# CurrentSensor.net
KiCad netlist of a schematic drawn in Altium Designer
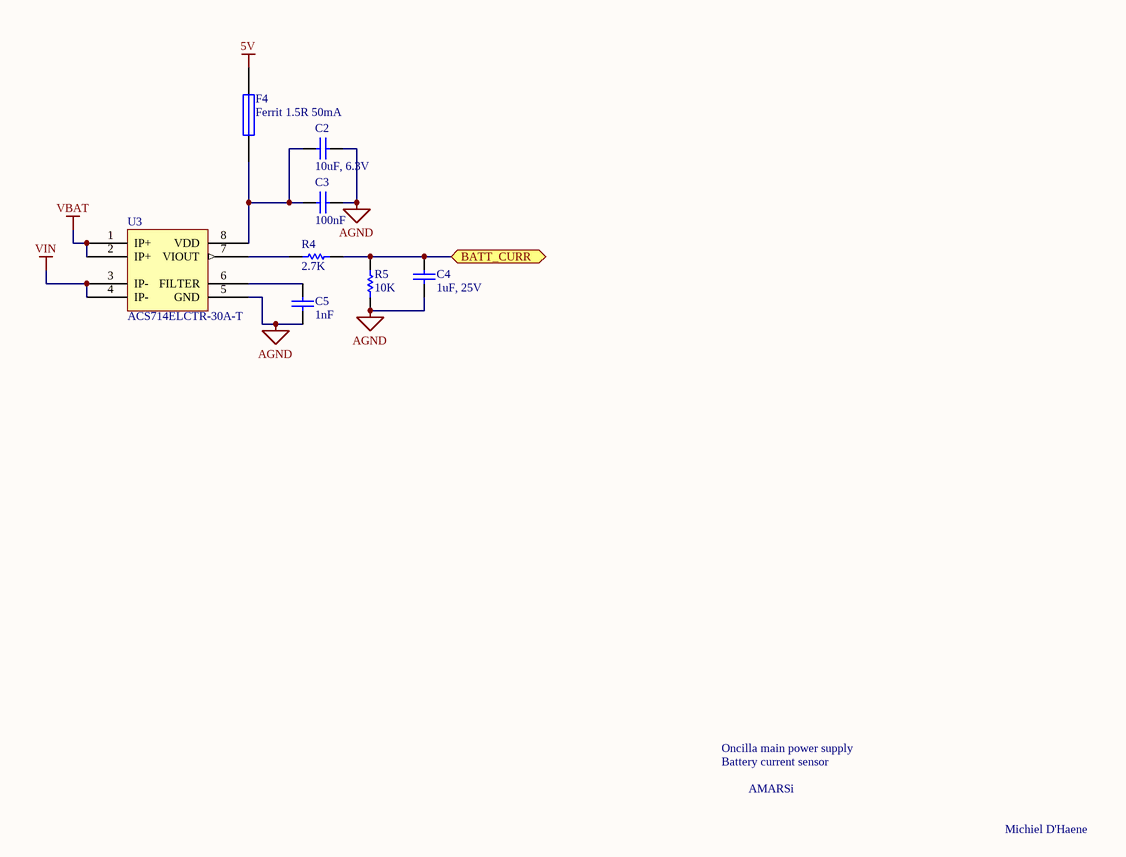
[diagram p0: CurrentSensor.SchDoc]

(export (version "E")
  (design (tool "Eeschema 10.0.6"))
  (components
    (comp (ref "C2")
      (value "10uF, 6.3V")
      (footprint "CAPC1608L")
      (description "Capacitor (Semiconductor SIM Model)")
      (fields (field (name "PUBLISHER") "Altium Limited"))
      (libsource (lib "Miscellaneous Devices") (part "Cap Semi"))
    )
    (comp (ref "C3")
      (value "100nF")
      (footprint "CAPC1608L")
      (description "Capacitor (Semiconductor SIM Model)")
      (fields (field (name "PUBLISHER") "Altium Limited"))
      (libsource (lib "Miscellaneous Devices") (part "Cap Semi"))
    )
    (comp (ref "C4")
      (value "1uF, 25V")
      (footprint "CAPC1608L")
      (description "Capacitor (Semiconductor SIM Model)")
      (fields (field (name "PUBLISHER") "Altium Limited"))
      (libsource (lib "Miscellaneous Devices") (part "Cap Semi"))
    )
    (comp (ref "C5")
      (value "1nF")
      (footprint "CAPC1608L")
      (description "Capacitor (Semiconductor SIM Model)")
      (fields (field (name "PUBLISHER") "Altium Limited"))
      (libsource (lib "Miscellaneous Devices") (part "Cap Semi"))
    )
    (comp (ref "F4")
      (value "Ferrit 1.5R 50mA")
      (footprint "RESC1608L")
      (description "Ferrit Bead")
      (fields (field (name "PUBLISHER") "Altium Limited"))
      (libsource (lib "Miscellaneous Devices") (part "Fuse 1"))
    )
    (comp (ref "R4")
      (value "2.7K")
      (footprint "RESC1608L")
      (description "Semiconductor Resistor")
      (fields (field (name "Comment") "2.7k") (field (name "PUBLISHER") "Altium Limited"))
      (libsource (lib "Miscellaneous Devices") (part "Res Semi"))
    )
    (comp (ref "R5")
      (value "10K")
      (footprint "RESC1608L")
      (description "Semiconductor Resistor")
      (fields (field (name "Comment") "10k") (field (name "PUBLISHER") "Altium Limited"))
      (libsource (lib "Miscellaneous Devices") (part "Res Semi"))
    )
    (comp (ref "U3")
      (value "ACS714ELCTR-30A-T")
      (footprint "SOIC-8_M")
      (description "Hall Effect-Based Linear Current Sensor")
      (libsource (lib "Roombots") (part "ACS714"))
    )
  )
  (nets
    (net (code "1") (name "/BATT_CURR") (class "Default")
      (node (ref "C4") (pin "2") (pinfunction "2_2") (pintype "passive"))
      (node (ref "R4") (pin "1") (pinfunction "1_1") (pintype "passive"))
      (node (ref "R5") (pin "2") (pinfunction "2_2") (pintype "passive"))
    )
    (net (code "2") (name "5V") (class "Default")
      (node (ref "F4") (pin "2") (pinfunction "2_2") (pintype "passive"))
    )
    (net (code "3") (name "AGND") (class "Default")
      (node (ref "C2") (pin "2") (pinfunction "2_2") (pintype "passive"))
      (node (ref "C3") (pin "2") (pinfunction "2_2") (pintype "passive"))
      (node (ref "C4") (pin "1") (pinfunction "1_1") (pintype "passive"))
      (node (ref "C5") (pin "1") (pinfunction "1_1") (pintype "passive"))
      (node (ref "R5") (pin "1") (pinfunction "1_1") (pintype "passive"))
      (node (ref "U3") (pin "5") (pinfunction "GND_5") (pintype "power_in"))
    )
    (net (code "4") (name "Net-(U3-FILTER)") (class "Default")
      (node (ref "C5") (pin "2") (pinfunction "2_2") (pintype "passive"))
      (node (ref "U3") (pin "6") (pinfunction "FILTER_6") (pintype "passive"))
    )
    (net (code "5") (name "Net-(U3-VDD)") (class "Default")
      (node (ref "C2") (pin "1") (pinfunction "1_1") (pintype "passive"))
      (node (ref "C3") (pin "1") (pinfunction "1_1") (pintype "passive"))
      (node (ref "F4") (pin "1") (pinfunction "1_1") (pintype "passive"))
      (node (ref "U3") (pin "8") (pinfunction "VDD_8") (pintype "power_in"))
    )
    (net (code "6") (name "Net-(U3-VIOUT)") (class "Default")
      (node (ref "R4") (pin "2") (pinfunction "2_2") (pintype "passive"))
      (node (ref "U3") (pin "7") (pinfunction "VIOUT_7") (pintype "output"))
    )
    (net (code "7") (name "VBAT") (class "Default")
      (node (ref "U3") (pin "1") (pinfunction "IP+_1") (pintype "passive"))
      (node (ref "U3") (pin "2") (pinfunction "IP+_2") (pintype "passive"))
    )
    (net (code "8") (name "VIN") (class "Default")
      (node (ref "U3") (pin "3") (pinfunction "IP-_3") (pintype "passive"))
      (node (ref "U3") (pin "4") (pinfunction "IP-_4") (pintype "passive"))
    )
  )
)
